# sonar-breakout.net
KiCad netlist of a schematic drawn in EAGLE
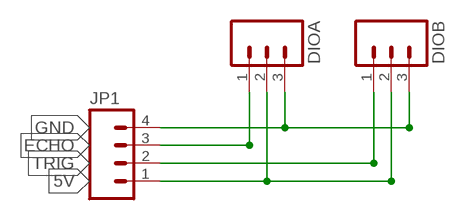
[diagram p0: schematic, sheet 1]

(export (version "E")
  (design (tool "Eeschema 10.0.6"))
  (components
    (comp (ref "DIOA")
      (value "M03LOCK")
      (footprint "eagle-import:1X03_LOCK")
      (libsource (lib "eagle-import") (part "M03LOCK"))
    )
    (comp (ref "DIOB")
      (value "M03LOCK")
      (footprint "eagle-import:1X03_LOCK")
      (libsource (lib "eagle-import") (part "M03LOCK"))
    )
    (comp (ref "JP1")
      (value "M04LOCK")
      (footprint "eagle-import:1X04_LOCK")
      (libsource (lib "eagle-import") (part "M04LOCK"))
    )
  )
  (nets
    (net (code "1") (name "5V") (class "Default")
      (node (ref "DIOA") (pin "2") (pinfunction "2_2") (pintype "passive"))
      (node (ref "DIOB") (pin "2") (pinfunction "2_2") (pintype "passive"))
      (node (ref "JP1") (pin "1") (pinfunction "1_1") (pintype "passive"))
    )
    (net (code "2") (name "ECHO") (class "Default")
      (node (ref "DIOA") (pin "1") (pinfunction "1_1") (pintype "passive"))
      (node (ref "JP1") (pin "3") (pinfunction "3_3") (pintype "passive"))
    )
    (net (code "3") (name "GND") (class "Default")
      (node (ref "DIOA") (pin "3") (pinfunction "3_3") (pintype "passive"))
      (node (ref "DIOB") (pin "3") (pinfunction "3_3") (pintype "passive"))
      (node (ref "JP1") (pin "4") (pinfunction "4_4") (pintype "passive"))
    )
    (net (code "4") (name "TRIG") (class "Default")
      (node (ref "DIOB") (pin "1") (pinfunction "1_1") (pintype "passive"))
      (node (ref "JP1") (pin "2") (pinfunction "2_2") (pintype "passive"))
    )
  )
)
